# industrialPrototype.net
KiCad netlist of a schematic drawn in EAGLE
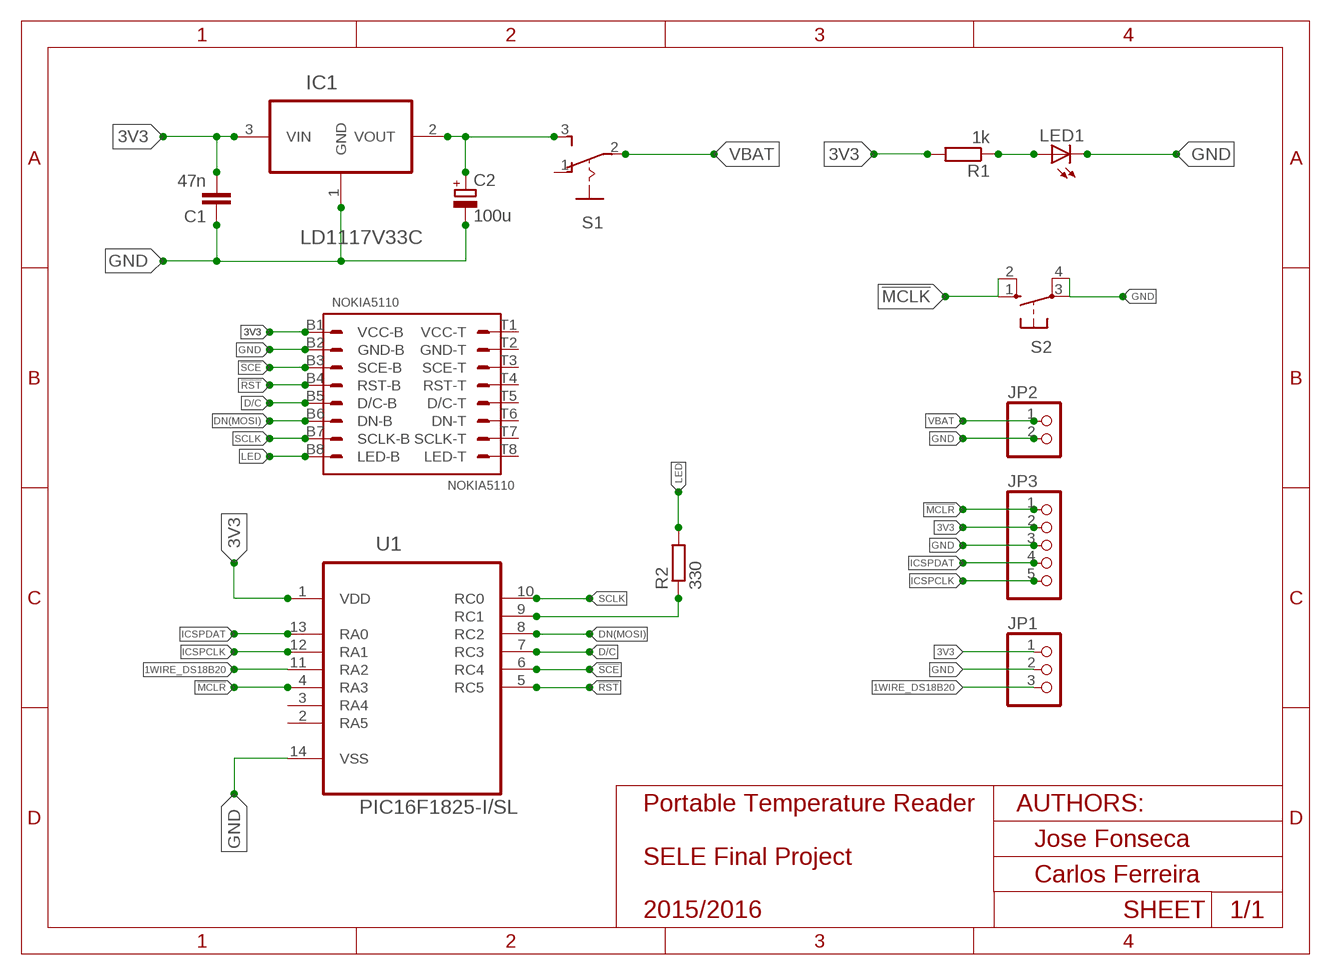
[diagram p0: schematic, sheet 1]

(export (version "E")
  (design (tool "Eeschema 10.0.6"))
  (components
    (comp (ref "C1")
      (value "47n")
      (footprint "eagle-import:C025-025X050")
      (libsource (lib "eagle-import") (part "C-EU025-025X050"))
    )
    (comp (ref "C2")
      (value "100u")
      (footprint "eagle-import:E2,5-6")
      (libsource (lib "eagle-import") (part "CPOL-EUE2.5-6"))
    )
    (comp (ref "IC1")
      (value "LD1117V33C")
      (footprint "eagle-import:TO254P482X1024X3124-3P")
      (libsource (lib "eagle-import") (part "LD1117V33C"))
    )
    (comp (ref "JP1")
      (value "PINHD-1X3")
      (footprint "eagle-import:1X03")
      (libsource (lib "eagle-import") (part "PINHD-1X3"))
    )
    (comp (ref "JP2")
      (value "PINHD-1X2")
      (footprint "eagle-import:1X02")
      (libsource (lib "eagle-import") (part "PINHD-1X2"))
    )
    (comp (ref "JP3")
      (value "PINHD-1X5")
      (footprint "eagle-import:1X05")
      (libsource (lib "eagle-import") (part "PINHD-1X5"))
    )
    (comp (ref "LED1")
      (value "LED3MM")
      (footprint "eagle-import:LED3MM")
      (libsource (lib "eagle-import") (part "LED3MM"))
    )
    (comp (ref "NOKIA5110")
      (value "NOKIA5110")
      (footprint "eagle-import:NOKIA5110")
      (libsource (lib "eagle-import") (part "NOKIA5110"))
    )
    (comp (ref "R1")
      (value "1k")
      (footprint "eagle-import:0204_5")
      (libsource (lib "eagle-import") (part "R-EU_0204/5"))
    )
    (comp (ref "R2")
      (value "330")
      (footprint "eagle-import:0204_5")
      (libsource (lib "eagle-import") (part "R-EU_0204/5"))
    )
    (comp (ref "S1")
      (value "255SB")
      (footprint "eagle-import:255SB")
      (libsource (lib "eagle-import") (part "255SB"))
    )
    (comp (ref "S2")
      (value "10-XX")
      (footprint "eagle-import:B3F-10XX")
      (fields (field (name "MPN") "B3F-1000"))
      (libsource (lib "eagle-import") (part "10-XX"))
    )
    (comp (ref "U1")
      (value "PIC16F1825-I/SL")
      (footprint "eagle-import:SOIC127P600X175-14N")
      (libsource (lib "eagle-import") (part "PIC16F1825-I/SL"))
    )
  )
  (nets
    (net (code "1") (name "/~{MCLK}") (class "Default")
      (node (ref "S2") (pin "1") (pinfunction "S_1") (pintype "passive"))
      (node (ref "S2") (pin "2") (pinfunction "S1_2") (pintype "passive"))
    )
    (net (code "2") (name "/~{MCLR}") (class "Default")
      (node (ref "JP3") (pin "1") (pinfunction "1_1") (pintype "passive"))
      (node (ref "U1") (pin "4") (pinfunction "RA3_4") (pintype "input"))
    )
    (net (code "3") (name "/~{RST}") (class "Default")
      (node (ref "NOKIA5110") (pin "B4") (pinfunction "RST-B_B4") (pintype "bidirectional"))
      (node (ref "U1") (pin "5") (pinfunction "RC5_5") (pintype "bidirectional"))
    )
    (net (code "4") (name "/~{SCE}") (class "Default")
      (node (ref "NOKIA5110") (pin "B3") (pinfunction "SCE-B_B3") (pintype "bidirectional"))
      (node (ref "U1") (pin "6") (pinfunction "RC4_6") (pintype "bidirectional"))
    )
    (net (code "5") (name "1WIRE_DS18B20") (class "Default")
      (node (ref "JP1") (pin "3") (pinfunction "3_3") (pintype "passive"))
      (node (ref "U1") (pin "11") (pinfunction "RA2_11") (pintype "bidirectional"))
    )
    (net (code "6") (name "3V3") (class "Default")
      (node (ref "C1") (pin "2") (pinfunction "2_2") (pintype "passive"))
      (node (ref "IC1") (pin "3") (pinfunction "VIN_3") (pintype "input"))
      (node (ref "JP1") (pin "1") (pinfunction "1_1") (pintype "passive"))
      (node (ref "JP3") (pin "2") (pinfunction "2_2") (pintype "passive"))
      (node (ref "NOKIA5110") (pin "B1") (pinfunction "VCC-B_B1") (pintype "bidirectional"))
      (node (ref "R1") (pin "2") (pinfunction "2_2") (pintype "passive"))
      (node (ref "U1") (pin "1") (pinfunction "VDD_1") (pintype "power_in"))
    )
    (net (code "7") (name "DN(MOSI)") (class "Default")
      (node (ref "NOKIA5110") (pin "B6") (pinfunction "DN-B_B6") (pintype "bidirectional"))
      (node (ref "U1") (pin "8") (pinfunction "RC2_8") (pintype "bidirectional"))
    )
    (net (code "8") (name "D{slash}C") (class "Default")
      (node (ref "NOKIA5110") (pin "B5") (pinfunction "D/C-B_B5") (pintype "bidirectional"))
      (node (ref "U1") (pin "7") (pinfunction "RC3_7") (pintype "bidirectional"))
    )
    (net (code "9") (name "GND") (class "Default")
      (node (ref "C1") (pin "1") (pinfunction "1_1") (pintype "passive"))
      (node (ref "C2") (pin "-") (pinfunction "-_-") (pintype "passive"))
      (node (ref "IC1") (pin "1") (pinfunction "GND_1") (pintype "passive"))
      (node (ref "JP1") (pin "2") (pinfunction "2_2") (pintype "passive"))
      (node (ref "JP2") (pin "2") (pinfunction "2_2") (pintype "passive"))
      (node (ref "JP3") (pin "3") (pinfunction "3_3") (pintype "passive"))
      (node (ref "LED1") (pin "K") (pinfunction "C_K") (pintype "passive"))
      (node (ref "NOKIA5110") (pin "B2") (pinfunction "GND-B_B2") (pintype "bidirectional"))
      (node (ref "S2") (pin "3") (pinfunction "P_3") (pintype "passive"))
      (node (ref "S2") (pin "4") (pinfunction "P1_4") (pintype "passive"))
      (node (ref "U1") (pin "14") (pinfunction "VSS_14") (pintype "passive"))
    )
    (net (code "10") (name "ICSPCLK") (class "Default")
      (node (ref "JP3") (pin "5") (pinfunction "5_5") (pintype "passive"))
      (node (ref "U1") (pin "12") (pinfunction "RA1_12") (pintype "bidirectional"))
    )
    (net (code "11") (name "ICSPDAT") (class "Default")
      (node (ref "JP3") (pin "4") (pinfunction "4_4") (pintype "passive"))
      (node (ref "U1") (pin "13") (pinfunction "RA0_13") (pintype "bidirectional"))
    )
    (net (code "12") (name "LED") (class "Default")
      (node (ref "NOKIA5110") (pin "B8") (pinfunction "LED-B_B8") (pintype "bidirectional"))
      (node (ref "R2") (pin "2") (pinfunction "2_2") (pintype "passive"))
    )
    (net (code "13") (name "Net-(LED1-PadA)") (class "Default")
      (node (ref "LED1") (pin "A") (pinfunction "A_A") (pintype "passive"))
      (node (ref "R1") (pin "1") (pinfunction "1_1") (pintype "passive"))
    )
    (net (code "14") (name "Net-(U1-RC1)") (class "Default")
      (node (ref "R2") (pin "1") (pinfunction "1_1") (pintype "passive"))
      (node (ref "U1") (pin "9") (pinfunction "RC1_9") (pintype "bidirectional"))
    )
    (net (code "15") (name "SCLK") (class "Default")
      (node (ref "NOKIA5110") (pin "B7") (pinfunction "SCLK-B_B7") (pintype "bidirectional"))
      (node (ref "U1") (pin "10") (pinfunction "RC0_10") (pintype "bidirectional"))
    )
    (net (code "16") (name "VBAT") (class "Default")
      (node (ref "C2") (pin "+") (pinfunction "+_+") (pintype "passive"))
      (node (ref "IC1") (pin "2") (pinfunction "VOUT_2") (pintype "output"))
      (node (ref "JP2") (pin "1") (pinfunction "1_1") (pintype "passive"))
      (node (ref "S1") (pin "2") (pinfunction "P_2") (pintype "passive"))
      (node (ref "S1") (pin "3") (pinfunction "S_3") (pintype "passive"))
    )
    (net (code "17") (name "unconnected-(NOKIA5110-DN-T-PadT6)") (class "Default")
      (node (ref "NOKIA5110") (pin "T6") (pinfunction "DN-T_T6") (pintype "bidirectional"))
    )
    (net (code "18") (name "unconnected-(NOKIA5110-D{slash}C-T-PadT5)") (class "Default")
      (node (ref "NOKIA5110") (pin "T5") (pinfunction "D/C-T_T5") (pintype "bidirectional"))
    )
    (net (code "19") (name "unconnected-(NOKIA5110-GND-T-PadT2)") (class "Default")
      (node (ref "NOKIA5110") (pin "T2") (pinfunction "GND-T_T2") (pintype "bidirectional"))
    )
    (net (code "20") (name "unconnected-(NOKIA5110-LED-T-PadT8)") (class "Default")
      (node (ref "NOKIA5110") (pin "T8") (pinfunction "LED-T_T8") (pintype "bidirectional"))
    )
    (net (code "21") (name "unconnected-(NOKIA5110-RST-T-PadT4)") (class "Default")
      (node (ref "NOKIA5110") (pin "T4") (pinfunction "RST-T_T4") (pintype "bidirectional"))
    )
    (net (code "22") (name "unconnected-(NOKIA5110-SCE-T-PadT3)") (class "Default")
      (node (ref "NOKIA5110") (pin "T3") (pinfunction "SCE-T_T3") (pintype "bidirectional"))
    )
    (net (code "23") (name "unconnected-(NOKIA5110-SCLK-T-PadT7)") (class "Default")
      (node (ref "NOKIA5110") (pin "T7") (pinfunction "SCLK-T_T7") (pintype "bidirectional"))
    )
    (net (code "24") (name "unconnected-(NOKIA5110-VCC-T-PadT1)") (class "Default")
      (node (ref "NOKIA5110") (pin "T1") (pinfunction "VCC-T_T1") (pintype "bidirectional"))
    )
    (net (code "25") (name "unconnected-(S1-O-Pad1)") (class "Default")
      (node (ref "S1") (pin "1") (pinfunction "O_1") (pintype "passive"))
    )
    (net (code "26") (name "unconnected-(U1-RA4-Pad3)") (class "Default")
      (node (ref "U1") (pin "3") (pinfunction "RA4_3") (pintype "bidirectional"))
    )
    (net (code "27") (name "unconnected-(U1-RA5-Pad2)") (class "Default")
      (node (ref "U1") (pin "2") (pinfunction "RA5_2") (pintype "bidirectional"))
    )
  )
)
